# USB_Hub.net
KiCad netlist of a schematic drawn in Altium Designer
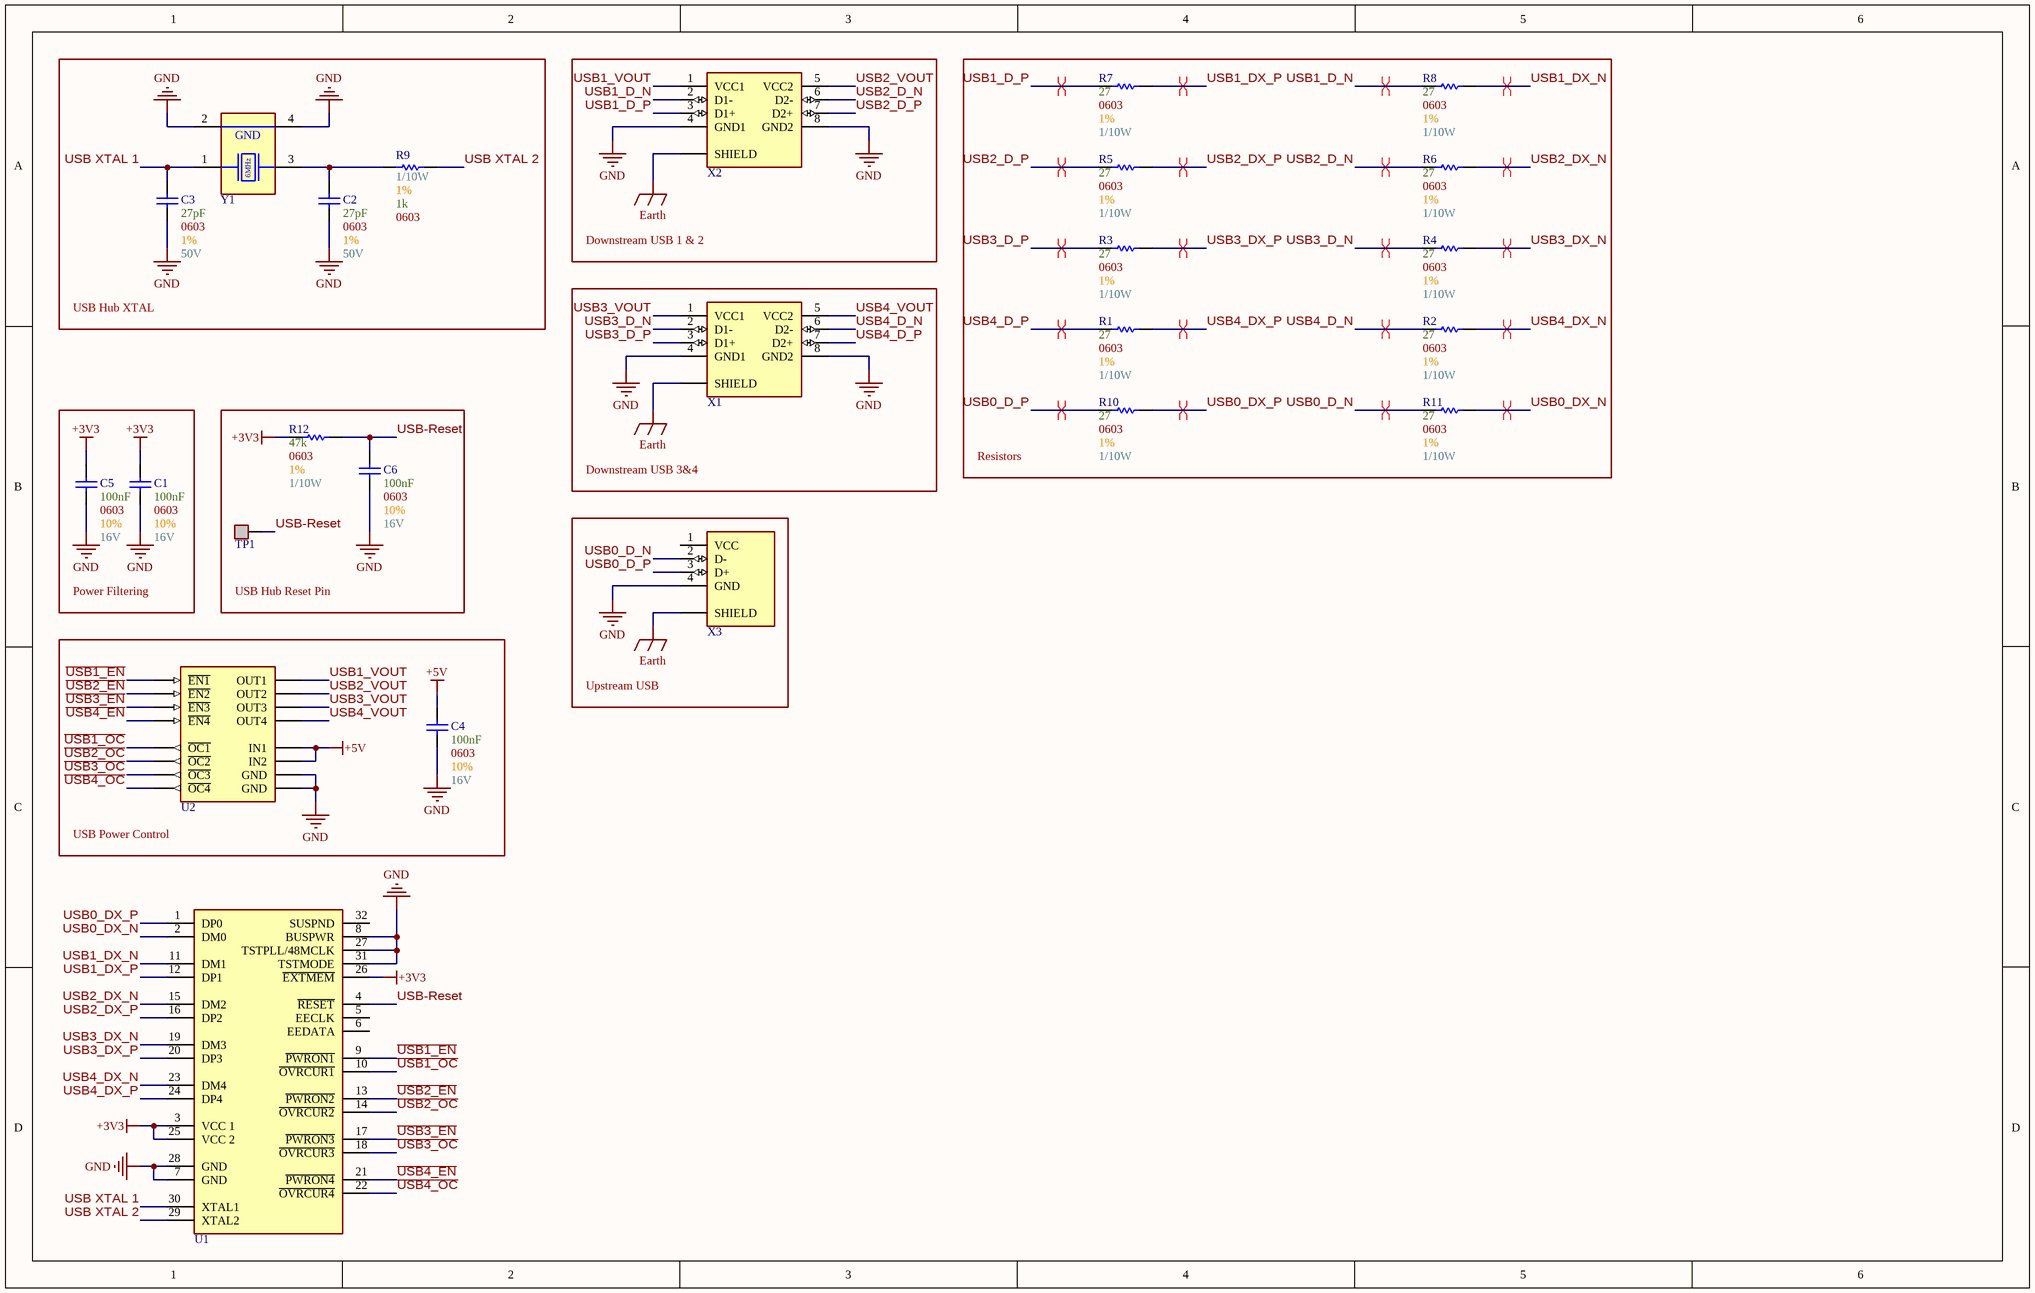
[diagram p0: USB Hub.SchDoc]

(export (version "E")
  (design (tool "Eeschema 10.0.6"))
  (components
    (comp (ref "C1")
      (value "[Cap] 0603 0.1uF 10% 16V")
      (footprint "[Cap] SMD 0603")
      (description "CC0603KRX7R7BB104")
      (fields
        (field (name "MAX VOLTAGE") "16V")
        (field (name "SIZE PACKAGE") "0603")
        (field (name "TOLERANCE") "10%")
        (field (name "CAPACITANCE") "100nF")
      )
      (libsource (lib "Capacitors") (part "[Cap] 0603 0.1uF 10% 16V"))
    )
    (comp (ref "C2")
      (value "[Cap] 0603 27pF 1% 50V")
      (footprint "[Cap] SMD 0603")
      (description "0603N270F500CT")
      (fields
        (field (name "MAX VOLTAGE") "50V")
        (field (name "SIZE PACKAGE") "0603")
        (field (name "TOLERANCE") "1%")
        (field (name "CAPACITANCE") "27pF")
      )
      (libsource (lib "Capacitors") (part "[Cap] 0603 27pF 1% 50V"))
    )
    (comp (ref "C3")
      (value "[Cap] 0603 27pF 1% 50V")
      (footprint "[Cap] SMD 0603")
      (description "0603N270F500CT")
      (fields
        (field (name "MAX VOLTAGE") "50V")
        (field (name "SIZE PACKAGE") "0603")
        (field (name "TOLERANCE") "1%")
        (field (name "CAPACITANCE") "27pF")
      )
      (libsource (lib "Capacitors") (part "[Cap] 0603 27pF 1% 50V"))
    )
    (comp (ref "C4")
      (value "[Cap] 0603 0.1uF 10% 16V")
      (footprint "[Cap] SMD 0603")
      (description "CC0603KRX7R7BB104")
      (fields
        (field (name "MAX VOLTAGE") "16V")
        (field (name "SIZE PACKAGE") "0603")
        (field (name "TOLERANCE") "10%")
        (field (name "CAPACITANCE") "100nF")
      )
      (libsource (lib "Capacitors") (part "[Cap] 0603 0.1uF 10% 16V"))
    )
    (comp (ref "C5")
      (value "[Cap] 0603 0.1uF 10% 16V")
      (footprint "[Cap] SMD 0603")
      (description "CC0603KRX7R7BB104")
      (fields
        (field (name "MAX VOLTAGE") "16V")
        (field (name "SIZE PACKAGE") "0603")
        (field (name "TOLERANCE") "10%")
        (field (name "CAPACITANCE") "100nF")
      )
      (libsource (lib "Capacitors") (part "[Cap] 0603 0.1uF 10% 16V"))
    )
    (comp (ref "C6")
      (value "[Cap] 0603 0.1uF 10% 16V")
      (footprint "[Cap] SMD 0603")
      (description "CC0603KRX7R7BB104")
      (fields
        (field (name "MAX VOLTAGE") "16V")
        (field (name "SIZE PACKAGE") "0603")
        (field (name "TOLERANCE") "10%")
        (field (name "CAPACITANCE") "100nF")
      )
      (libsource (lib "Capacitors") (part "[Cap] 0603 0.1uF 10% 16V"))
    )
    (comp (ref "R1")
      (value "[27] SMD 0603 1% 1/10W")
      (footprint "[Res] SMD 0603")
      (description "MCT06030C2709FP500")
      (fields
        (field (name "WATTAGE") "1/10W")
        (field (name "TOLERANCE") "1%")
        (field (name "RESISTANCE") "27")
        (field (name "SIZE PACKAGE") "0603")
      )
      (libsource (lib "Resistors") (part "[27] SMD 0603 1% 1/10W"))
    )
    (comp (ref "R2")
      (value "[27] SMD 0603 1% 1/10W")
      (footprint "[Res] SMD 0603")
      (description "MCT06030C2709FP500")
      (fields
        (field (name "WATTAGE") "1/10W")
        (field (name "TOLERANCE") "1%")
        (field (name "RESISTANCE") "27")
        (field (name "SIZE PACKAGE") "0603")
      )
      (libsource (lib "Resistors") (part "[27] SMD 0603 1% 1/10W"))
    )
    (comp (ref "R3")
      (value "[27] SMD 0603 1% 1/10W")
      (footprint "[Res] SMD 0603")
      (description "MCT06030C2709FP500")
      (fields
        (field (name "WATTAGE") "1/10W")
        (field (name "TOLERANCE") "1%")
        (field (name "RESISTANCE") "27")
        (field (name "SIZE PACKAGE") "0603")
      )
      (libsource (lib "Resistors") (part "[27] SMD 0603 1% 1/10W"))
    )
    (comp (ref "R4")
      (value "[27] SMD 0603 1% 1/10W")
      (footprint "[Res] SMD 0603")
      (description "MCT06030C2709FP500")
      (fields
        (field (name "WATTAGE") "1/10W")
        (field (name "TOLERANCE") "1%")
        (field (name "RESISTANCE") "27")
        (field (name "SIZE PACKAGE") "0603")
      )
      (libsource (lib "Resistors") (part "[27] SMD 0603 1% 1/10W"))
    )
    (comp (ref "R5")
      (value "[27] SMD 0603 1% 1/10W")
      (footprint "[Res] SMD 0603")
      (description "MCT06030C2709FP500")
      (fields
        (field (name "WATTAGE") "1/10W")
        (field (name "TOLERANCE") "1%")
        (field (name "RESISTANCE") "27")
        (field (name "SIZE PACKAGE") "0603")
      )
      (libsource (lib "Resistors") (part "[27] SMD 0603 1% 1/10W"))
    )
    (comp (ref "R6")
      (value "[27] SMD 0603 1% 1/10W")
      (footprint "[Res] SMD 0603")
      (description "MCT06030C2709FP500")
      (fields
        (field (name "WATTAGE") "1/10W")
        (field (name "TOLERANCE") "1%")
        (field (name "RESISTANCE") "27")
        (field (name "SIZE PACKAGE") "0603")
      )
      (libsource (lib "Resistors") (part "[27] SMD 0603 1% 1/10W"))
    )
    (comp (ref "R7")
      (value "[27] SMD 0603 1% 1/10W")
      (footprint "[Res] SMD 0603")
      (description "MCT06030C2709FP500")
      (fields
        (field (name "WATTAGE") "1/10W")
        (field (name "TOLERANCE") "1%")
        (field (name "RESISTANCE") "27")
        (field (name "SIZE PACKAGE") "0603")
      )
      (libsource (lib "Resistors") (part "[27] SMD 0603 1% 1/10W"))
    )
    (comp (ref "R8")
      (value "[27] SMD 0603 1% 1/10W")
      (footprint "[Res] SMD 0603")
      (description "MCT06030C2709FP500")
      (fields
        (field (name "WATTAGE") "1/10W")
        (field (name "TOLERANCE") "1%")
        (field (name "RESISTANCE") "27")
        (field (name "SIZE PACKAGE") "0603")
      )
      (libsource (lib "Resistors") (part "[27] SMD 0603 1% 1/10W"))
    )
    (comp (ref "R9")
      (value "[1k] SMD 0603 1% 1/10W")
      (footprint "[Res] SMD 0603")
      (description "RMCF0603FT1K00")
      (fields
        (field (name "WATTAGE") "1/10W")
        (field (name "TOLERANCE") "1%")
        (field (name "RESISTANCE") "1k")
        (field (name "SIZE PACKAGE") "0603")
      )
      (libsource (lib "Resistors") (part "[1k] SMD 0603 1% 1/10W"))
    )
    (comp (ref "R10")
      (value "[27] SMD 0603 1% 1/10W")
      (footprint "[Res] SMD 0603")
      (description "MCT06030C2709FP500")
      (fields
        (field (name "WATTAGE") "1/10W")
        (field (name "TOLERANCE") "1%")
        (field (name "RESISTANCE") "27")
        (field (name "SIZE PACKAGE") "0603")
      )
      (libsource (lib "Resistors") (part "[27] SMD 0603 1% 1/10W"))
    )
    (comp (ref "R11")
      (value "[27] SMD 0603 1% 1/10W")
      (footprint "[Res] SMD 0603")
      (description "MCT06030C2709FP500")
      (fields
        (field (name "WATTAGE") "1/10W")
        (field (name "TOLERANCE") "1%")
        (field (name "RESISTANCE") "27")
        (field (name "SIZE PACKAGE") "0603")
      )
      (libsource (lib "Resistors") (part "[27] SMD 0603 1% 1/10W"))
    )
    (comp (ref "R12")
      (value "[47k] SMD 0603 1% 1/10W")
      (footprint "[Res] SMD 0603")
      (description "RC0603FR-0747KL")
      (fields
        (field (name "WATTAGE") "1/10W")
        (field (name "TOLERANCE") "1%")
        (field (name "RESISTANCE") "47k")
        (field (name "SIZE PACKAGE") "0603")
      )
      (libsource (lib "Resistors") (part "[47k] SMD 0603 1% 1/10W"))
    )
    (comp (ref "TP1")
      (value "[THM] Thru-Hole")
      (footprint "[THM] White")
      (description "5012")
      (libsource (lib "Test Points") (part "[THM] Thru-Hole"))
    )
    (comp (ref "U1")
      (value "4port")
      (footprint "[USB Hub] USB2.0 4port")
      (description "TUSB2046BVFR")
      (libsource (lib "ICs") (part "[USB Hub] USB 2.0 4port"))
    )
    (comp (ref "U2")
      (value "[USB Power] 500mA 4port")
      (footprint "[IC] USB Hub Power Distribution")
      (description "TPS2044BDR")
      (libsource (lib "ICs") (part "[USB Power] 500mA 4port"))
    )
    (comp (ref "X1")
      (value "USB-A")
      (footprint "[USB] Type-A Dual")
      (description "61400826021")
      (libsource (lib "Connectors") (part "[USB] Type-A Dual"))
    )
    (comp (ref "X2")
      (value "USB-A")
      (footprint "[USB] Type-A Dual")
      (description "61400826021")
      (libsource (lib "Connectors") (part "[USB] Type-A Dual"))
    )
    (comp (ref "X3")
      (value "USB-A")
      (footprint "[USB] Type-A")
      (description "KUSBEX-ASFS1N-B")
      (libsource (lib "Connectors") (part "[USB] Type-A"))
    )
    (comp (ref "Y1")
      (value "[Crystal] SMD 6MHz")
      (footprint "[Crystal] SMD 6MHz")
      (description "ECS-060-18-20BM-JEN-TR")
      (libsource (lib "Crystals and Oscillators") (part "[Crystal] SMD 6MHz"))
    )
  )
  (nets
    (net (code "1") (name "+3V3") (class "Default")
      (node (ref "C1") (pin "2") (pinfunction "2_2") (pintype "passive"))
      (node (ref "C5") (pin "2") (pinfunction "2_2") (pintype "passive"))
      (node (ref "R12") (pin "1") (pinfunction "1_1") (pintype "passive"))
      (node (ref "U1") (pin "25") (pinfunction "VCC_2_25") (pintype "passive"))
      (node (ref "U1") (pin "26") (pinfunction "~{EXTMEM}_26") (pintype "passive"))
      (node (ref "U1") (pin "3") (pinfunction "VCC_1_3") (pintype "passive"))
    )
    (net (code "2") (name "+5V") (class "Default")
      (node (ref "C4") (pin "2") (pinfunction "2_2") (pintype "passive"))
      (node (ref "U2") (pin "2") (pinfunction "IN1_2") (pintype "power_in"))
      (node (ref "U2") (pin "6") (pinfunction "IN2_6") (pintype "power_in"))
    )
    (net (code "3") (name "/USB XTAL 1") (class "Default")
      (node (ref "C3") (pin "2") (pinfunction "2_2") (pintype "passive"))
      (node (ref "U1") (pin "30") (pinfunction "XTAL1_30") (pintype "passive"))
      (node (ref "Y1") (pin "1") (pinfunction "XTAL1_1") (pintype "power_in"))
    )
    (net (code "4") (name "/USB XTAL 2") (class "Default")
      (node (ref "R9") (pin "2") (pinfunction "2_2") (pintype "passive"))
      (node (ref "U1") (pin "29") (pinfunction "XTAL2_29") (pintype "passive"))
    )
    (net (code "5") (name "/USB-Reset") (class "Default")
      (node (ref "C6") (pin "2") (pinfunction "2_2") (pintype "passive"))
      (node (ref "R12") (pin "2") (pinfunction "2_2") (pintype "passive"))
      (node (ref "TP1") (pin "1") (pinfunction "1_1") (pintype "passive"))
      (node (ref "U1") (pin "4") (pinfunction "~{RESET}_4") (pintype "passive"))
    )
    (net (code "6") (name "/USB0_DX_N") (class "Default")
      (node (ref "R11") (pin "2") (pinfunction "2_2") (pintype "passive"))
      (node (ref "U1") (pin "2") (pinfunction "DM0_2") (pintype "passive"))
    )
    (net (code "7") (name "/USB0_DX_P") (class "Default")
      (node (ref "R10") (pin "2") (pinfunction "2_2") (pintype "passive"))
      (node (ref "U1") (pin "1") (pinfunction "DP0_1") (pintype "passive"))
    )
    (net (code "8") (name "/USB0_D_N") (class "Default")
      (node (ref "R11") (pin "1") (pinfunction "1_1") (pintype "passive"))
      (node (ref "X3") (pin "2") (pinfunction "D-_2") (pintype "bidirectional"))
    )
    (net (code "9") (name "/USB0_D_P") (class "Default")
      (node (ref "R10") (pin "1") (pinfunction "1_1") (pintype "passive"))
      (node (ref "X3") (pin "3") (pinfunction "D+_3") (pintype "bidirectional"))
    )
    (net (code "10") (name "/USB1_DX_N") (class "Default")
      (node (ref "R8") (pin "2") (pinfunction "2_2") (pintype "passive"))
      (node (ref "U1") (pin "11") (pinfunction "DM1_11") (pintype "passive"))
    )
    (net (code "11") (name "/USB1_DX_P") (class "Default")
      (node (ref "R7") (pin "2") (pinfunction "2_2") (pintype "passive"))
      (node (ref "U1") (pin "12") (pinfunction "DP1_12") (pintype "passive"))
    )
    (net (code "12") (name "/USB1_D_N") (class "Default")
      (node (ref "R8") (pin "1") (pinfunction "1_1") (pintype "passive"))
      (node (ref "X2") (pin "2") (pinfunction "D1-_2") (pintype "bidirectional"))
    )
    (net (code "13") (name "/USB1_D_P") (class "Default")
      (node (ref "R7") (pin "1") (pinfunction "1_1") (pintype "passive"))
      (node (ref "X2") (pin "3") (pinfunction "D1+_3") (pintype "bidirectional"))
    )
    (net (code "14") (name "/USB1_EN") (class "Default")
      (node (ref "U1") (pin "9") (pinfunction "~{PWRON1}_9") (pintype "passive"))
      (node (ref "U2") (pin "3") (pinfunction "~{EN1}_3") (pintype "input"))
    )
    (net (code "15") (name "/USB1_OC") (class "Default")
      (node (ref "U1") (pin "10") (pinfunction "~{OVRCUR1}_10") (pintype "passive"))
      (node (ref "U2") (pin "16") (pinfunction "~{OC1}_16") (pintype "output"))
    )
    (net (code "16") (name "/USB1_VOUT") (class "Default")
      (node (ref "U2") (pin "15") (pinfunction "OUT1_15") (pintype "power_in"))
      (node (ref "X2") (pin "1") (pinfunction "VCC1_1") (pintype "power_in"))
    )
    (net (code "17") (name "/USB2_DX_N") (class "Default")
      (node (ref "R6") (pin "2") (pinfunction "2_2") (pintype "passive"))
      (node (ref "U1") (pin "15") (pinfunction "DM2_15") (pintype "passive"))
    )
    (net (code "18") (name "/USB2_DX_P") (class "Default")
      (node (ref "R5") (pin "2") (pinfunction "2_2") (pintype "passive"))
      (node (ref "U1") (pin "16") (pinfunction "DP2_16") (pintype "passive"))
    )
    (net (code "19") (name "/USB2_D_N") (class "Default")
      (node (ref "R6") (pin "1") (pinfunction "1_1") (pintype "passive"))
      (node (ref "X2") (pin "6") (pinfunction "D2-_6") (pintype "bidirectional"))
    )
    (net (code "20") (name "/USB2_D_P") (class "Default")
      (node (ref "R5") (pin "1") (pinfunction "1_1") (pintype "passive"))
      (node (ref "X2") (pin "7") (pinfunction "D2+_7") (pintype "bidirectional"))
    )
    (net (code "21") (name "/USB2_EN") (class "Default")
      (node (ref "U1") (pin "13") (pinfunction "~{PWRON2}_13") (pintype "passive"))
      (node (ref "U2") (pin "4") (pinfunction "~{EN2}_4") (pintype "input"))
    )
    (net (code "22") (name "/USB2_OC") (class "Default")
      (node (ref "U1") (pin "14") (pinfunction "~{OVRCUR2}_14") (pintype "passive"))
      (node (ref "U2") (pin "13") (pinfunction "~{OC2}_13") (pintype "output"))
    )
    (net (code "23") (name "/USB2_VOUT") (class "Default")
      (node (ref "U2") (pin "14") (pinfunction "OUT2_14") (pintype "power_in"))
      (node (ref "X2") (pin "5") (pinfunction "VCC2_5") (pintype "power_in"))
    )
    (net (code "24") (name "/USB3_DX_N") (class "Default")
      (node (ref "R4") (pin "2") (pinfunction "2_2") (pintype "passive"))
      (node (ref "U1") (pin "19") (pinfunction "DM3_19") (pintype "passive"))
    )
    (net (code "25") (name "/USB3_DX_P") (class "Default")
      (node (ref "R3") (pin "2") (pinfunction "2_2") (pintype "passive"))
      (node (ref "U1") (pin "20") (pinfunction "DP3_20") (pintype "passive"))
    )
    (net (code "26") (name "/USB3_D_N") (class "Default")
      (node (ref "R4") (pin "1") (pinfunction "1_1") (pintype "passive"))
      (node (ref "X1") (pin "2") (pinfunction "D1-_2") (pintype "bidirectional"))
    )
    (net (code "27") (name "/USB3_D_P") (class "Default")
      (node (ref "R3") (pin "1") (pinfunction "1_1") (pintype "passive"))
      (node (ref "X1") (pin "3") (pinfunction "D1+_3") (pintype "bidirectional"))
    )
    (net (code "28") (name "/USB3_EN") (class "Default")
      (node (ref "U1") (pin "17") (pinfunction "~{PWRON3}_17") (pintype "passive"))
      (node (ref "U2") (pin "7") (pinfunction "~{EN3}_7") (pintype "input"))
    )
    (net (code "29") (name "/USB3_OC") (class "Default")
      (node (ref "U1") (pin "18") (pinfunction "~{OVRCUR3}_18") (pintype "passive"))
      (node (ref "U2") (pin "12") (pinfunction "~{OC3}_12") (pintype "output"))
    )
    (net (code "30") (name "/USB3_VOUT") (class "Default")
      (node (ref "U2") (pin "11") (pinfunction "OUT3_11") (pintype "power_in"))
      (node (ref "X1") (pin "1") (pinfunction "VCC1_1") (pintype "power_in"))
    )
    (net (code "31") (name "/USB4_DX_N") (class "Default")
      (node (ref "R2") (pin "2") (pinfunction "2_2") (pintype "passive"))
      (node (ref "U1") (pin "23") (pinfunction "DM4_23") (pintype "passive"))
    )
    (net (code "32") (name "/USB4_DX_P") (class "Default")
      (node (ref "R1") (pin "2") (pinfunction "2_2") (pintype "passive"))
      (node (ref "U1") (pin "24") (pinfunction "DP4_24") (pintype "passive"))
    )
    (net (code "33") (name "/USB4_D_N") (class "Default")
      (node (ref "R2") (pin "1") (pinfunction "1_1") (pintype "passive"))
      (node (ref "X1") (pin "6") (pinfunction "D2-_6") (pintype "bidirectional"))
    )
    (net (code "34") (name "/USB4_D_P") (class "Default")
      (node (ref "R1") (pin "1") (pinfunction "1_1") (pintype "passive"))
      (node (ref "X1") (pin "7") (pinfunction "D2+_7") (pintype "bidirectional"))
    )
    (net (code "35") (name "/USB4_EN") (class "Default")
      (node (ref "U1") (pin "21") (pinfunction "~{PWRON4}_21") (pintype "passive"))
      (node (ref "U2") (pin "8") (pinfunction "~{EN4}_8") (pintype "input"))
    )
    (net (code "36") (name "/USB4_OC") (class "Default")
      (node (ref "U1") (pin "22") (pinfunction "~{OVRCUR4}_22") (pintype "passive"))
      (node (ref "U2") (pin "9") (pinfunction "~{OC4}_9") (pintype "output"))
    )
    (net (code "37") (name "/USB4_VOUT") (class "Default")
      (node (ref "U2") (pin "10") (pinfunction "OUT4_10") (pintype "power_in"))
      (node (ref "X1") (pin "5") (pinfunction "VCC2_5") (pintype "power_in"))
    )
    (net (code "38") (name "Earth") (class "Default")
      (node (ref "X1") (pin "MH") (pinfunction "SHIELD_MH") (pintype "passive"))
      (node (ref "X2") (pin "MH") (pinfunction "SHIELD_MH") (pintype "passive"))
      (node (ref "X3") (pin "MH") (pinfunction "SHIELD_MH") (pintype "passive"))
    )
    (net (code "39") (name "GND") (class "Default")
      (node (ref "C1") (pin "1") (pinfunction "1_1") (pintype "passive"))
      (node (ref "C2") (pin "1") (pinfunction "1_1") (pintype "passive"))
      (node (ref "C3") (pin "1") (pinfunction "1_1") (pintype "passive"))
      (node (ref "C4") (pin "1") (pinfunction "1_1") (pintype "passive"))
      (node (ref "C5") (pin "1") (pinfunction "1_1") (pintype "passive"))
      (node (ref "C6") (pin "1") (pinfunction "1_1") (pintype "passive"))
      (node (ref "U1") (pin "27") (pinfunction "TSTPLL/48MCLK_27") (pintype "passive"))
      (node (ref "U1") (pin "28") (pinfunction "GND_28") (pintype "passive"))
      (node (ref "U1") (pin "31") (pinfunction "TSTMODE_31") (pintype "passive"))
      (node (ref "U1") (pin "7") (pinfunction "GND_7") (pintype "passive"))
      (node (ref "U1") (pin "8") (pinfunction "BUSPWR_8") (pintype "passive"))
      (node (ref "U2") (pin "1") (pinfunction "GND_1") (pintype "power_in"))
      (node (ref "U2") (pin "5") (pinfunction "GND_5") (pintype "power_in"))
      (node (ref "X1") (pin "4") (pinfunction "GND1_4") (pintype "power_in"))
      (node (ref "X1") (pin "8") (pinfunction "GND2_8") (pintype "power_in"))
      (node (ref "X2") (pin "4") (pinfunction "GND1_4") (pintype "power_in"))
      (node (ref "X2") (pin "8") (pinfunction "GND2_8") (pintype "power_in"))
      (node (ref "X3") (pin "4") (pinfunction "GND_4") (pintype "power_in"))
      (node (ref "Y1") (pin "2") (pinfunction "GND_2") (pintype "power_in"))
      (node (ref "Y1") (pin "4") (pinfunction "GND_4") (pintype "power_in"))
    )
    (net (code "40") (name "Net-(Y1-XTAL2)") (class "Default")
      (node (ref "C2") (pin "2") (pinfunction "2_2") (pintype "passive"))
      (node (ref "R9") (pin "1") (pinfunction "1_1") (pintype "passive"))
      (node (ref "Y1") (pin "3") (pinfunction "XTAL2_3") (pintype "power_in"))
    )
    (net (code "41") (name "unconnected-(U1-EECLK-Pad5)") (class "Default")
      (node (ref "U1") (pin "5") (pinfunction "EECLK_5") (pintype "passive"))
    )
    (net (code "42") (name "unconnected-(U1-EEDATA-Pad6)") (class "Default")
      (node (ref "U1") (pin "6") (pinfunction "EEDATA_6") (pintype "passive"))
    )
    (net (code "43") (name "unconnected-(U1-SUSPND-Pad32)") (class "Default")
      (node (ref "U1") (pin "32") (pinfunction "SUSPND_32") (pintype "passive"))
    )
    (net (code "44") (name "unconnected-(X3-VCC-Pad1)") (class "Default")
      (node (ref "X3") (pin "1") (pinfunction "VCC_1") (pintype "power_in"))
    )
  )
)
